# schematic.net
KiCad netlist of a schematic drawn in EAGLE
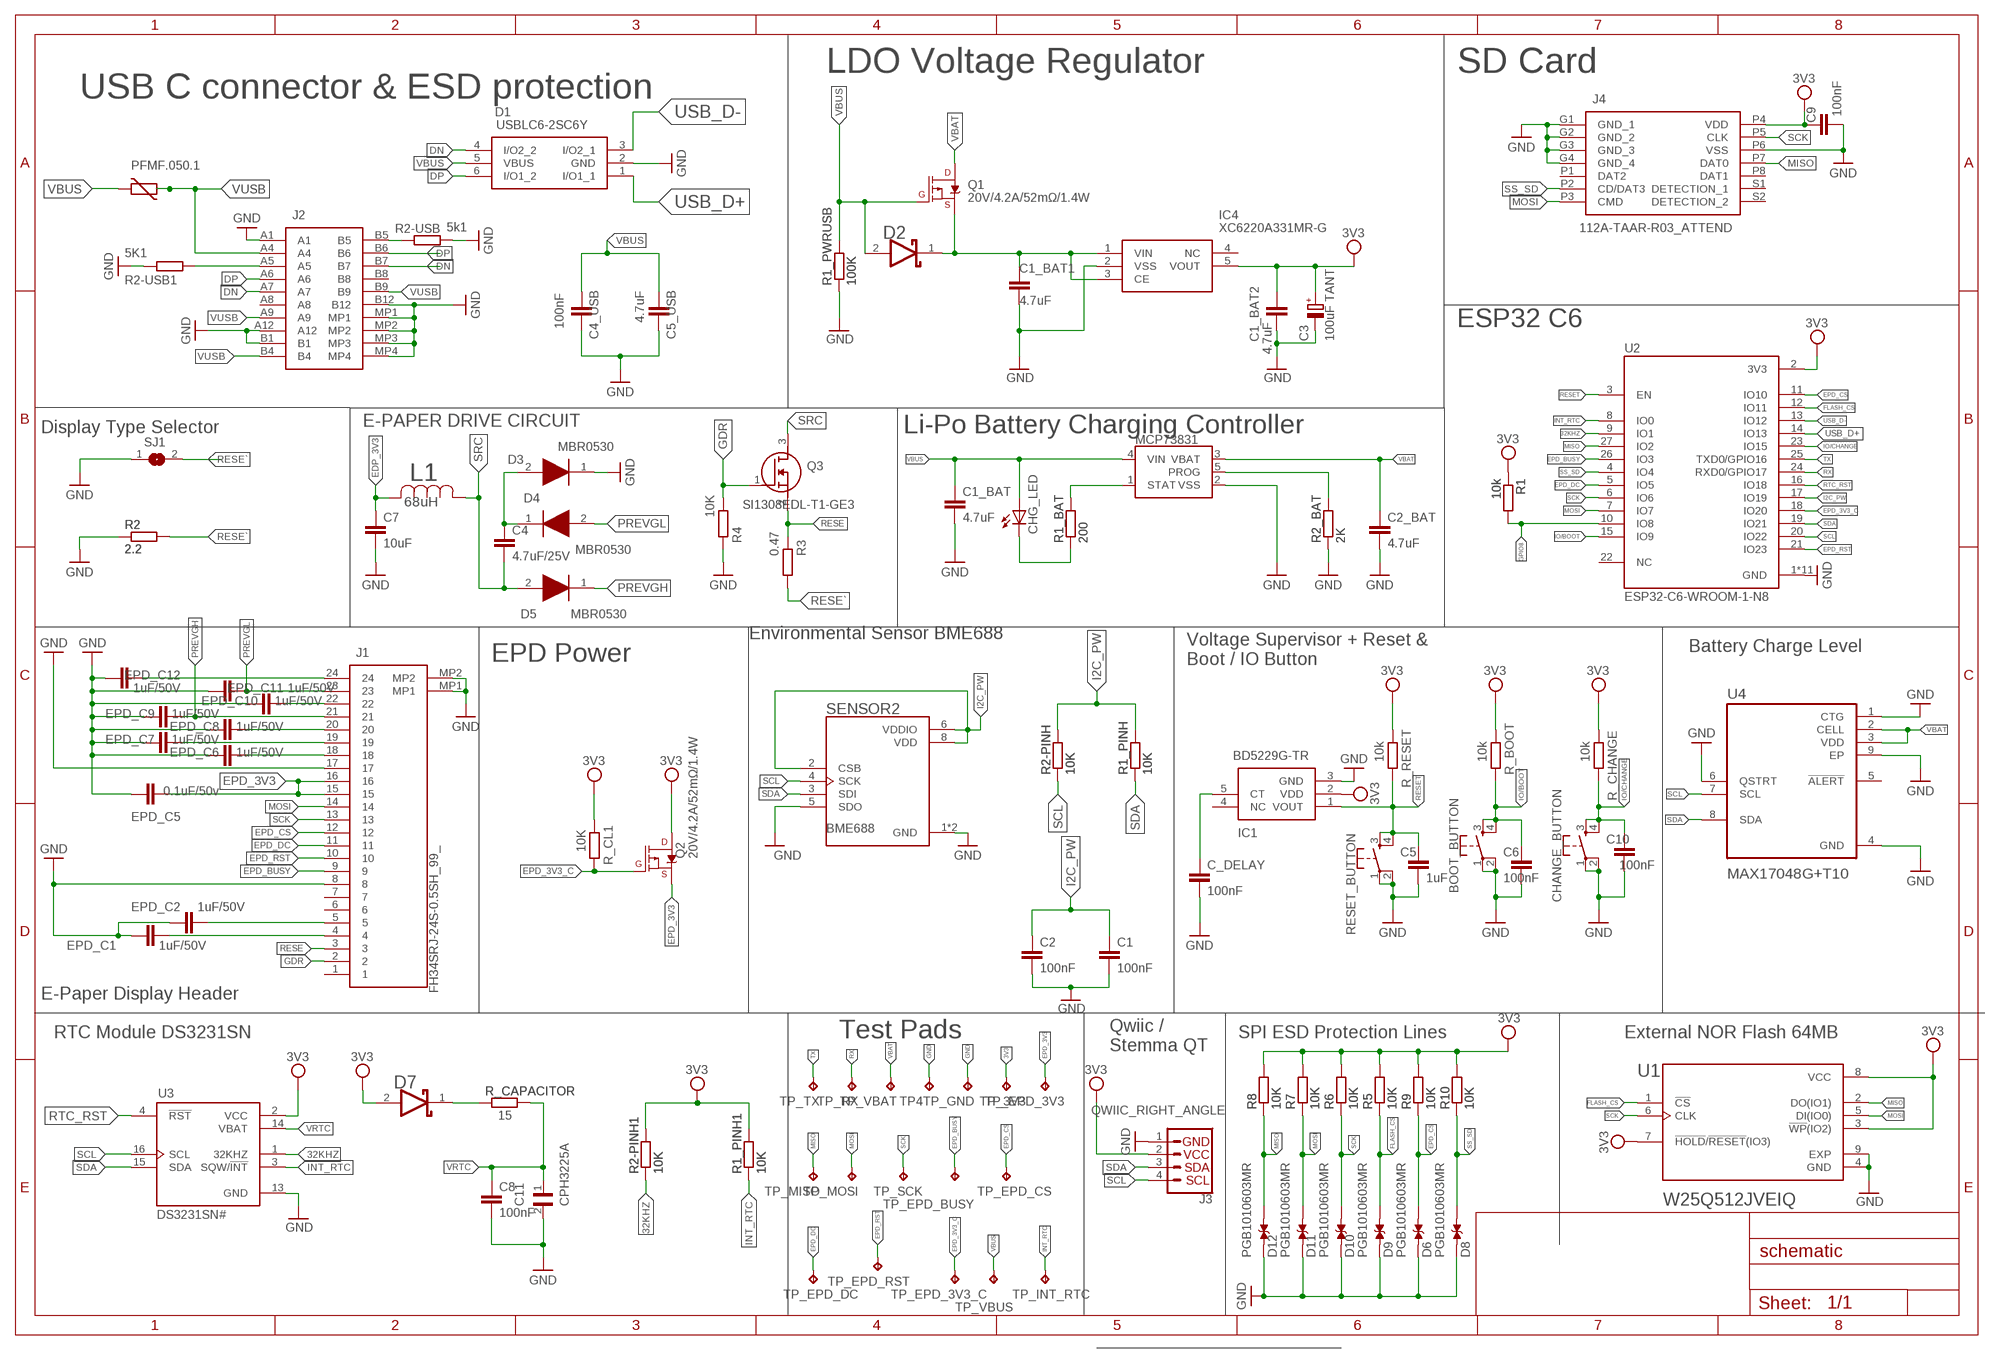
[diagram p0: schematic, sheet 1]

(export (version "E")
  (design (tool "Eeschema 10.0.6"))
  (components
    (comp (ref "BOOT_BUTTON")
      (value "BUTTON_CUSYOMV1")
      (footprint "eagle-import:MYBUTTON")
      (libsource (lib "eagle-import") (part "BUTTON_CUSYOMV1"))
    )
    (comp (ref "C1")
      (value "100nF")
      (footprint "eagle-import:EAGLE-LTSPICE_C0402")
      (libsource (lib "eagle-import") (part "EAGLE-LTSPICE_CC0402"))
    )
    (comp (ref "C1_BAT")
      (value "4.7uF")
      (footprint "eagle-import:EAGLE-LTSPICE_C0402")
      (libsource (lib "eagle-import") (part "EAGLE-LTSPICE_CC0402"))
    )
    (comp (ref "C1_BAT1")
      (value "4.7uF")
      (footprint "eagle-import:ESP32_WROVER_EAGLE-LTSPICE_C0402")
      (libsource (lib "eagle-import") (part "ESP32_WROVER_EAGLE-LTSPICE_CC0402"))
    )
    (comp (ref "C1_BAT2")
      (value "4.7uF")
      (footprint "eagle-import:ESP32_WROVER_EAGLE-LTSPICE_C0402")
      (libsource (lib "eagle-import") (part "ESP32_WROVER_EAGLE-LTSPICE_CC0402"))
    )
    (comp (ref "C2")
      (value "100nF")
      (footprint "eagle-import:EAGLE-LTSPICE_C0402")
      (libsource (lib "eagle-import") (part "EAGLE-LTSPICE_CC0402"))
    )
    (comp (ref "C2_BAT")
      (value "4.7uF")
      (footprint "eagle-import:EAGLE-LTSPICE_C0402")
      (libsource (lib "eagle-import") (part "EAGLE-LTSPICE_CC0402"))
    )
    (comp (ref "C3")
      (value "100uF TANT")
      (footprint "eagle-import:RCL_CT3528")
      (libsource (lib "eagle-import") (part "RCL_CPOL-EUCT3528"))
    )
    (comp (ref "C4")
      (value "4.7uF/25V")
      (footprint "eagle-import:EAGLE-LTSPICE_C0402")
      (libsource (lib "eagle-import") (part "EAGLE-LTSPICE_CC0402"))
    )
    (comp (ref "C4_USB")
      (value "100nF")
      (footprint "eagle-import:EAGLE-LTSPICE_C0402")
      (libsource (lib "eagle-import") (part "EAGLE-LTSPICE_CC0402"))
    )
    (comp (ref "C5")
      (value "1uF")
      (footprint "eagle-import:EAGLE-LTSPICE_C0402")
      (libsource (lib "eagle-import") (part "EAGLE-LTSPICE_CC0402"))
    )
    (comp (ref "C5_USB")
      (value "4.7uF")
      (footprint "eagle-import:EAGLE-LTSPICE_C0402")
      (libsource (lib "eagle-import") (part "EAGLE-LTSPICE_CC0402"))
    )
    (comp (ref "C6")
      (value "100nF")
      (footprint "eagle-import:EAGLE-LTSPICE_C0402")
      (libsource (lib "eagle-import") (part "EAGLE-LTSPICE_CC0402"))
    )
    (comp (ref "C7")
      (value "10uF")
      (footprint "eagle-import:EAGLE-LTSPICE_C0402")
      (libsource (lib "eagle-import") (part "EAGLE-LTSPICE_CC0402"))
    )
    (comp (ref "C8")
      (value "100nF")
      (footprint "eagle-import:EAGLE-LTSPICE_C0402")
      (libsource (lib "eagle-import") (part "EAGLE-LTSPICE_CC0402"))
    )
    (comp (ref "C9")
      (value "100nF")
      (footprint "eagle-import:EAGLE-LTSPICE_C0402")
      (libsource (lib "eagle-import") (part "EAGLE-LTSPICE_CC0402"))
    )
    (comp (ref "C10")
      (value "100nF")
      (footprint "eagle-import:EAGLE-LTSPICE_C0402")
      (libsource (lib "eagle-import") (part "EAGLE-LTSPICE_CC0402"))
    )
    (comp (ref "C11")
      (value "CPH3225A")
      (footprint "eagle-import:CAPCP3225X100N")
      (fields (field (name "MF") "Seiko Instruments"))
      (libsource (lib "eagle-import") (part "CPH3225A"))
    )
    (comp (ref "CHANGE_BUTTON")
      (value "BUTTON_CUSYOMV1")
      (footprint "eagle-import:MYBUTTON")
      (libsource (lib "eagle-import") (part "BUTTON_CUSYOMV1"))
    )
    (comp (ref "CHG_LED")
      (value "ADAFRUIT_LEDCHIP-LED0603")
      (footprint "eagle-import:ADAFRUIT_CHIP-LED0603")
      (libsource (lib "eagle-import") (part "ADAFRUIT_LEDCHIP-LED0603"))
    )
    (comp (ref "C_DELAY")
      (value "100nF")
      (footprint "eagle-import:EAGLE-LTSPICE_C0402")
      (libsource (lib "eagle-import") (part "EAGLE-LTSPICE_CC0402"))
    )
    (comp (ref "D1")
      (value "USBLC6-2SC6Y")
      (footprint "eagle-import:SOT95P280X145-6N")
      (fields (field (name "MF") "STMicroelectronics"))
      (libsource (lib "eagle-import") (part "USBLC6-2SC6Y"))
    )
    (comp (ref "D2")
      (value "ESP32_WROVER_AVX---SD0805S020S1R0_AVX_SD0805S020S1R0_0_0AVX_SD0805S020S1R0_0_0")
      (footprint "eagle-import:ESP32_WROVER_AVX---SD0805S020S1R0_AVX_SD0805S020S1R0_0")
      (fields
        (field (name "DIGIKEY_PART_NUMBER") "478-7800-1-ND")
        (field (name "MF") "AVX")
        (field (name "MOUSER_PART_NUMBER") "581-SD0805S020S1R0")
      )
      (libsource (lib "eagle-import") (part "ESP32_WROVER_AVX---SD0805S020S1R0_AVX_SD0805S020S1R0_0_0AVX_SD0805S020S1R0_0_0"))
    )
    (comp (ref "D3")
      (value "MBR0530")
      (footprint "eagle-import:SOD3716X135N")
      (fields (field (name "MF") "ON Semiconductor"))
      (libsource (lib "eagle-import") (part "MBR0530"))
    )
    (comp (ref "D4")
      (value "MBR0530")
      (footprint "eagle-import:SOD3716X135N")
      (fields (field (name "MF") "ON Semiconductor"))
      (libsource (lib "eagle-import") (part "MBR0530"))
    )
    (comp (ref "D5")
      (value "MBR0530")
      (footprint "eagle-import:SOD3716X135N")
      (fields (field (name "MF") "ON Semiconductor"))
      (libsource (lib "eagle-import") (part "MBR0530"))
    )
    (comp (ref "D6")
      (value "PGB1010603MR")
      (footprint "eagle-import:DIOC1608X36N")
      (fields (field (name "MF") "Littelfuse Inc."))
      (libsource (lib "eagle-import") (part "PGB1010603MR"))
    )
    (comp (ref "D7")
      (value "ESP32_WROVER_AVX---SD0805S020S1R0_AVX_SD0805S020S1R0_0_0AVX_SD0805S020S1R0_0_0")
      (footprint "eagle-import:ESP32_WROVER_AVX---SD0805S020S1R0_AVX_SD0805S020S1R0_0")
      (fields
        (field (name "DIGIKEY_PART_NUMBER") "478-7800-1-ND")
        (field (name "MF") "AVX")
        (field (name "MOUSER_PART_NUMBER") "581-SD0805S020S1R0")
      )
      (libsource (lib "eagle-import") (part "ESP32_WROVER_AVX---SD0805S020S1R0_AVX_SD0805S020S1R0_0_0AVX_SD0805S020S1R0_0_0"))
    )
    (comp (ref "D8")
      (value "PGB1010603MR")
      (footprint "eagle-import:DIOC1608X36N")
      (fields (field (name "MF") "Littelfuse Inc."))
      (libsource (lib "eagle-import") (part "PGB1010603MR"))
    )
    (comp (ref "D9")
      (value "PGB1010603MR")
      (footprint "eagle-import:DIOC1608X36N")
      (fields (field (name "MF") "Littelfuse Inc."))
      (libsource (lib "eagle-import") (part "PGB1010603MR"))
    )
    (comp (ref "D10")
      (value "PGB1010603MR")
      (footprint "eagle-import:DIOC1608X36N")
      (fields (field (name "MF") "Littelfuse Inc."))
      (libsource (lib "eagle-import") (part "PGB1010603MR"))
    )
    (comp (ref "D11")
      (value "PGB1010603MR")
      (footprint "eagle-import:DIOC1608X36N")
      (fields (field (name "MF") "Littelfuse Inc."))
      (libsource (lib "eagle-import") (part "PGB1010603MR"))
    )
    (comp (ref "D12")
      (value "PGB1010603MR")
      (footprint "eagle-import:DIOC1608X36N")
      (fields (field (name "MF") "Littelfuse Inc."))
      (libsource (lib "eagle-import") (part "PGB1010603MR"))
    )
    (comp (ref "EPD_C1")
      (value "1uF/50V")
      (footprint "eagle-import:EAGLE-LTSPICE_C0402")
      (libsource (lib "eagle-import") (part "EAGLE-LTSPICE_CC0402"))
    )
    (comp (ref "EPD_C2")
      (value "1uF/50V")
      (footprint "eagle-import:EAGLE-LTSPICE_C0402")
      (libsource (lib "eagle-import") (part "EAGLE-LTSPICE_CC0402"))
    )
    (comp (ref "EPD_C5")
      (value "0.1uF/50v")
      (footprint "eagle-import:EAGLE-LTSPICE_C0402")
      (libsource (lib "eagle-import") (part "EAGLE-LTSPICE_CC0402"))
    )
    (comp (ref "EPD_C6")
      (value "1uF/50V")
      (footprint "eagle-import:EAGLE-LTSPICE_C0402")
      (libsource (lib "eagle-import") (part "EAGLE-LTSPICE_CC0402"))
    )
    (comp (ref "EPD_C7")
      (value "1uF/50V")
      (footprint "eagle-import:EAGLE-LTSPICE_C0402")
      (libsource (lib "eagle-import") (part "EAGLE-LTSPICE_CC0402"))
    )
    (comp (ref "EPD_C8")
      (value "1uF/50V")
      (footprint "eagle-import:EAGLE-LTSPICE_C0402")
      (libsource (lib "eagle-import") (part "EAGLE-LTSPICE_CC0402"))
    )
    (comp (ref "EPD_C9")
      (value "1uF/50V")
      (footprint "eagle-import:EAGLE-LTSPICE_C0402")
      (libsource (lib "eagle-import") (part "EAGLE-LTSPICE_CC0402"))
    )
    (comp (ref "EPD_C10")
      (value "1uF/50V")
      (footprint "eagle-import:EAGLE-LTSPICE_C0402")
      (libsource (lib "eagle-import") (part "EAGLE-LTSPICE_CC0402"))
    )
    (comp (ref "EPD_C11")
      (value "1uF/50V")
      (footprint "eagle-import:EAGLE-LTSPICE_C0402")
      (libsource (lib "eagle-import") (part "EAGLE-LTSPICE_CC0402"))
    )
    (comp (ref "EPD_C12")
      (value "1uF/50V")
      (footprint "eagle-import:EAGLE-LTSPICE_C0402")
      (libsource (lib "eagle-import") (part "EAGLE-LTSPICE_CC0402"))
    )
    (comp (ref "IC1")
      (value "BD5229G-TR")
      (footprint "eagle-import:SOT95P280X125-5N")
      (fields (field (name "MOUSER_PART_NUMBER") "755-BD5229G-TR"))
      (libsource (lib "eagle-import") (part "BD5229G-TR"))
    )
    (comp (ref "IC4")
      (value "XC6220A331MR-G")
      (footprint "eagle-import:SOT95P280X120-5N")
      (fields (field (name "MOUSER_PART_NUMBER") "865-XC6220A331MR-G"))
      (libsource (lib "eagle-import") (part "XC6220A331MR-G"))
    )
    (comp (ref "J1")
      (value "FH34SRJ-24S-0.5SH_99_")
      (footprint "eagle-import:FH34SRJ24S05SH99")
      (fields
        (field (name "MANUFACTURER_PART_NUMBER") "FH34SRJ-24S-0.5SH(99)")
        (field (name "MOUSER_PART_NUMBER") "798-FH34SRJ24S05SH99")
      )
      (libsource (lib "eagle-import") (part "FH34SRJ-24S-0.5SH_99_"))
    )
    (comp (ref "J2")
      (value "SAMACSYS_PARTS_USB4110-GF-A")
      (footprint "eagle-import:SAMACSYS_PARTS_USB4110GFA")
      (fields
        (field (name "MANUFACTURER_PART_NUMBER") "USB4110-GF-A")
        (field (name "MOUSER_PART_NUMBER") "640-USB4110-GF-A")
      )
      (libsource (lib "eagle-import") (part "SAMACSYS_PARTS_USB4110-GF-A"))
    )
    (comp (ref "J3")
      (value "QWIIC_RIGHT_ANGLE")
      (footprint "eagle-import:JST04_1MM_RA")
      (libsource (lib "eagle-import") (part "QWIIC_CONNECTORJS-1MM"))
    )
    (comp (ref "J4")
      (value "112A-TAAR-R03_ATTEND")
      (footprint "eagle-import:112ATAARR03ATTEND")
      (fields (field (name "MANUFACTURER_PART_NUMBER") "112A-TAAR-R03 ATTEND"))
      (libsource (lib "eagle-import") (part "112A-TAAR-R03_ATTEND"))
    )
    (comp (ref "L1")
      (value "68uH")
      (footprint "eagle-import:IND_4828-WE-TPC_WRE")
      (fields
        (field (name "MANUFACTURER_PART_NUMBER") "744043680")
        (field (name "COPYRIGHT") "Copyright (C) 2024 Ultra Librarian. All rights reserved.")
      )
      (libsource (lib "eagle-import") (part "744043680IND_4828-WE-TPC_WRE"))
    )
    (comp (ref "MCP73831")
      (value "ESP32_WROVER_SPARKFUN-IC-POWER_MCP73831")
      (footprint "eagle-import:ESP32_WROVER_SPARKFUN-IC-POWER_SOT23-5")
      (libsource (lib "eagle-import") (part "ESP32_WROVER_SPARKFUN-IC-POWER_MCP73831"))
    )
    (comp (ref "PFMF.050.1")
      (value "ESP32C6_VARISTORCN1812")
      (footprint "eagle-import:ESP32C6_VARISTOR_CT_CN1812")
      (libsource (lib "eagle-import") (part "ESP32C6_VARISTORCN1812"))
    )
    (comp (ref "Q1")
      (value "20V/4.2A/52mΩ/1.4W")
      (footprint "eagle-import:ESP32_WROVER_SPARKFUN-DISCRETESEMI_SOT23-3")
      (libsource (lib "eagle-import") (part "ESP32_WROVER_SPARKFUN-DISCRETESEMI_MOSFET_PCH-DMG2305UX-7"))
    )
    (comp (ref "Q2")
      (value "20V/4.2A/52mΩ/1.4W")
      (footprint "eagle-import:ESP32_WROVER_SPARKFUN-DISCRETESEMI_SOT23-3")
      (libsource (lib "eagle-import") (part "ESP32_WROVER_SPARKFUN-DISCRETESEMI_MOSFET_PCH-DMG2305UX-7"))
    )
    (comp (ref "Q3")
      (value "SI1308EDL-T1-GE3")
      (footprint "eagle-import:SOT65P210X110-3N")
      (fields (field (name "MF") "Vishay Siliconix"))
      (libsource (lib "eagle-import") (part "SI1308EDL-T1-GE3"))
    )
    (comp (ref "R1")
      (value "10k")
      (footprint "eagle-import:ESP32_WROVER_EAGLE-LTSPICE_R0402")
      (libsource (lib "eagle-import") (part "ESP32_WROVER_EAGLE-LTSPICE_RR0402"))
    )
    (comp (ref "R1_BAT")
      (value "200")
      (footprint "eagle-import:ESP32_WROVER_EAGLE-LTSPICE_R0402")
      (libsource (lib "eagle-import") (part "ESP32_WROVER_EAGLE-LTSPICE_RR0402"))
    )
    (comp (ref "R1_PINH")
      (value "10K")
      (footprint "eagle-import:ESP32_WROVER_EAGLE-LTSPICE_R0402")
      (libsource (lib "eagle-import") (part "ESP32_WROVER_EAGLE-LTSPICE_RR0402"))
    )
    (comp (ref "R1_PINH1")
      (value "10K")
      (footprint "eagle-import:ESP32_WROVER_EAGLE-LTSPICE_R0402")
      (libsource (lib "eagle-import") (part "ESP32_WROVER_EAGLE-LTSPICE_RR0402"))
    )
    (comp (ref "R1_PWRUSB")
      (value "100K")
      (footprint "eagle-import:ESP32_WROVER_EAGLE-LTSPICE_R0402")
      (libsource (lib "eagle-import") (part "ESP32_WROVER_EAGLE-LTSPICE_RR0402"))
    )
    (comp (ref "R2")
      (value "2.2")
      (footprint "eagle-import:ESP32_WROVER_EAGLE-LTSPICE_R0402")
      (libsource (lib "eagle-import") (part "ESP32_WROVER_EAGLE-LTSPICE_RR0402"))
    )
    (comp (ref "R2-PINH")
      (value "10K")
      (footprint "eagle-import:ESP32_WROVER_EAGLE-LTSPICE_R0402")
      (libsource (lib "eagle-import") (part "ESP32_WROVER_EAGLE-LTSPICE_RR0402"))
    )
    (comp (ref "R2-PINH1")
      (value "10K")
      (footprint "eagle-import:ESP32_WROVER_EAGLE-LTSPICE_R0402")
      (libsource (lib "eagle-import") (part "ESP32_WROVER_EAGLE-LTSPICE_RR0402"))
    )
    (comp (ref "R2-USB")
      (value "5k1")
      (footprint "eagle-import:ESP32_WROVER_EAGLE-LTSPICE_R0402")
      (libsource (lib "eagle-import") (part "ESP32_WROVER_EAGLE-LTSPICE_RR0402"))
    )
    (comp (ref "R2-USB1")
      (value "5K1")
      (footprint "eagle-import:ESP32_WROVER_EAGLE-LTSPICE_R0402")
      (fields (field (name "SPICEPREFIX") "R2-USB1"))
      (libsource (lib "eagle-import") (part "ESP32_WROVER_EAGLE-LTSPICE_RR0402"))
    )
    (comp (ref "R2_BAT")
      (value "2K")
      (footprint "eagle-import:ESP32_WROVER_EAGLE-LTSPICE_R0402")
      (libsource (lib "eagle-import") (part "ESP32_WROVER_EAGLE-LTSPICE_RR0402"))
    )
    (comp (ref "R3")
      (value "0.47")
      (footprint "eagle-import:ESP32_WROVER_EAGLE-LTSPICE_R0402")
      (libsource (lib "eagle-import") (part "ESP32_WROVER_EAGLE-LTSPICE_RR0402"))
    )
    (comp (ref "R4")
      (value "10K")
      (footprint "eagle-import:ESP32_WROVER_EAGLE-LTSPICE_R0402")
      (libsource (lib "eagle-import") (part "ESP32_WROVER_EAGLE-LTSPICE_RR0402"))
    )
    (comp (ref "R5")
      (value "10K")
      (footprint "eagle-import:ESP32_WROVER_EAGLE-LTSPICE_R0402")
      (libsource (lib "eagle-import") (part "ESP32_WROVER_EAGLE-LTSPICE_RR0402"))
    )
    (comp (ref "R6")
      (value "10K")
      (footprint "eagle-import:ESP32_WROVER_EAGLE-LTSPICE_R0402")
      (libsource (lib "eagle-import") (part "ESP32_WROVER_EAGLE-LTSPICE_RR0402"))
    )
    (comp (ref "R7")
      (value "10K")
      (footprint "eagle-import:ESP32_WROVER_EAGLE-LTSPICE_R0402")
      (libsource (lib "eagle-import") (part "ESP32_WROVER_EAGLE-LTSPICE_RR0402"))
    )
    (comp (ref "R8")
      (value "10K")
      (footprint "eagle-import:ESP32_WROVER_EAGLE-LTSPICE_R0402")
      (libsource (lib "eagle-import") (part "ESP32_WROVER_EAGLE-LTSPICE_RR0402"))
    )
    (comp (ref "R9")
      (value "10K")
      (footprint "eagle-import:ESP32_WROVER_EAGLE-LTSPICE_R0402")
      (libsource (lib "eagle-import") (part "ESP32_WROVER_EAGLE-LTSPICE_RR0402"))
    )
    (comp (ref "R10")
      (value "10K")
      (footprint "eagle-import:ESP32_WROVER_EAGLE-LTSPICE_R0402")
      (libsource (lib "eagle-import") (part "ESP32_WROVER_EAGLE-LTSPICE_RR0402"))
    )
    (comp (ref "RESET_BUTTON")
      (value "BUTTON_CUSYOMV1")
      (footprint "eagle-import:MYBUTTON")
      (libsource (lib "eagle-import") (part "BUTTON_CUSYOMV1"))
    )
    (comp (ref "R_BOOT")
      (value "10k")
      (footprint "eagle-import:ESP32_WROVER_EAGLE-LTSPICE_R0402")
      (libsource (lib "eagle-import") (part "ESP32_WROVER_EAGLE-LTSPICE_RR0402"))
    )
    (comp (ref "R_CAPACITOR")
      (value "15")
      (footprint "eagle-import:ESP32_WROVER_EAGLE-LTSPICE_R0402")
      (libsource (lib "eagle-import") (part "ESP32_WROVER_EAGLE-LTSPICE_RR0402"))
    )
    (comp (ref "R_CHANGE")
      (value "10k")
      (footprint "eagle-import:ESP32_WROVER_EAGLE-LTSPICE_R0402")
      (libsource (lib "eagle-import") (part "ESP32_WROVER_EAGLE-LTSPICE_RR0402"))
    )
    (comp (ref "R_CL1")
      (value "10K")
      (footprint "eagle-import:ESP32_WROVER_EAGLE-LTSPICE_R0402")
      (libsource (lib "eagle-import") (part "ESP32_WROVER_EAGLE-LTSPICE_RR0402"))
    )
    (comp (ref "R_RESET")
      (value "10k")
      (footprint "eagle-import:ESP32_WROVER_EAGLE-LTSPICE_R0402")
      (libsource (lib "eagle-import") (part "ESP32_WROVER_EAGLE-LTSPICE_RR0402"))
    )
    (comp (ref "SENSOR2")
      (value "ESP32_WROVER_BME680_BME680")
      (footprint "eagle-import:ESP32_WROVER_BME680_PSON80P300X300X100-8N")
      (fields (field (name "MF") "Bosch Sensortec") (field (name "MP") "BME680"))
      (libsource (lib "eagle-import") (part "ESP32_WROVER_BME680_BME680"))
    )
    (comp (ref "SJ1") (value "SJ") (footprint "eagle-import:SJ") (libsource (lib "eagle-import") (part "SJ")))
    (comp (ref "TP4")
      (value "TPTP20R")
      (footprint "eagle-import:TP20R")
      (libsource (lib "eagle-import") (part "TPTP20R"))
    )
    (comp (ref "TP_3V3")
      (value "TPTP20R")
      (footprint "eagle-import:TP20R")
      (libsource (lib "eagle-import") (part "TPTP20R"))
    )
    (comp (ref "TP_EPD_3V3")
      (value "TPTP20R")
      (footprint "eagle-import:TP20R")
      (libsource (lib "eagle-import") (part "TPTP20R"))
    )
    (comp (ref "TP_EPD_3V3_C")
      (value "TPTP20R")
      (footprint "eagle-import:TP20R")
      (libsource (lib "eagle-import") (part "TPTP20R"))
    )
    (comp (ref "TP_EPD_BUSY")
      (value "TPTP20R")
      (footprint "eagle-import:TP20R")
      (libsource (lib "eagle-import") (part "TPTP20R"))
    )
    (comp (ref "TP_EPD_CS")
      (value "TPTP20R")
      (footprint "eagle-import:TP20R")
      (libsource (lib "eagle-import") (part "TPTP20R"))
    )
    (comp (ref "TP_EPD_DC")
      (value "TPTP20R")
      (footprint "eagle-import:TP20R")
      (libsource (lib "eagle-import") (part "TPTP20R"))
    )
    (comp (ref "TP_EPD_RST")
      (value "TPTP20R")
      (footprint "eagle-import:TP20R")
      (libsource (lib "eagle-import") (part "TPTP20R"))
    )
    (comp (ref "TP_GND")
      (value "TPTP20R")
      (footprint "eagle-import:TP20R")
      (libsource (lib "eagle-import") (part "TPTP20R"))
    )
    (comp (ref "TP_INT_RTC")
      (value "TPTP20R")
      (footprint "eagle-import:TP20R")
      (libsource (lib "eagle-import") (part "TPTP20R"))
    )
    (comp (ref "TP_MISO")
      (value "TPTP20R")
      (footprint "eagle-import:TP20R")
      (libsource (lib "eagle-import") (part "TPTP20R"))
    )
    (comp (ref "TP_MOSI")
      (value "TPTP20R")
      (footprint "eagle-import:TP20R")
      (libsource (lib "eagle-import") (part "TPTP20R"))
    )
    (comp (ref "TP_RX")
      (value "TPTP20R")
      (footprint "eagle-import:TP20R")
      (libsource (lib "eagle-import") (part "TPTP20R"))
    )
    (comp (ref "TP_SCK")
      (value "TPTP20R")
      (footprint "eagle-import:TP20R")
      (libsource (lib "eagle-import") (part "TPTP20R"))
    )
    (comp (ref "TP_TX")
      (value "TPTP20R")
      (footprint "eagle-import:TP20R")
      (libsource (lib "eagle-import") (part "TPTP20R"))
    )
    (comp (ref "TP_VBAT")
      (value "TPTP20R")
      (footprint "eagle-import:TP20R")
      (libsource (lib "eagle-import") (part "TPTP20R"))
    )
    (comp (ref "TP_VBUS")
      (value "TPTP20R")
      (footprint "eagle-import:TP20R")
      (libsource (lib "eagle-import") (part "TPTP20R"))
    )
    (comp (ref "U1")
      (value "W25Q512JVEIQ")
      (footprint "eagle-import:SON127P600X800X80-9N")
      (fields (field (name "MF") "Winbond Electronics"))
      (libsource (lib "eagle-import") (part "W25Q512JVEIQ"))
    )
    (comp (ref "U2")
      (value "ESP32-C6-WROOM-1-N8")
      (footprint "eagle-import:XCVR_ESP32-C6-WROOM-1-N8")
      (fields (field (name "MF") "Espressif Systems"))
      (libsource (lib "eagle-import") (part "ESP32-C6-WROOM-1-N8"))
    )
    (comp (ref "U3")
      (value "DS3231SN#")
      (footprint "eagle-import:SOIC127P1032X265-16N")
      (fields (field (name "MF") "Analog Devices"))
      (libsource (lib "eagle-import") (part "DS3231SN#"))
    )
    (comp (ref "U4")
      (value "MAX17048G+T10")
      (footprint "eagle-import:SON50P200X200X80-9N")
      (fields (field (name "MF") "Analog Devices"))
      (libsource (lib "eagle-import") (part "MAX17048G+T10"))
    )
  )
  (nets
    (net (code "1") (name "3V3") (class "Default")
      (node (ref "C1_BAT2") (pin "1") (pinfunction "1_1") (pintype "passive"))
      (node (ref "C3") (pin "+") (pinfunction "+_+") (pintype "passive"))
      (node (ref "C9") (pin "2") (pinfunction "2_2") (pintype "passive"))
      (node (ref "D7") (pin "2") (pinfunction "ANODE_2") (pintype "bidirectional"))
      (node (ref "IC1") (pin "2") (pinfunction "VDD_2") (pintype "bidirectional"))
      (node (ref "IC4") (pin "5") (pinfunction "VOUT_5") (pintype "bidirectional"))
      (node (ref "J3") (pin "2") (pinfunction "2_2") (pintype "power_in"))
      (node (ref "J4") (pin "P4") (pinfunction "VDD_P4") (pintype "bidirectional"))
      (node (ref "Q2") (pin "3") (pinfunction "D_3") (pintype "bidirectional"))
      (node (ref "R1") (pin "1") (pinfunction "1_1") (pintype "passive"))
      (node (ref "R10") (pin "2") (pinfunction "2_2") (pintype "passive"))
      (node (ref "R1_PINH1") (pin "2") (pinfunction "2_2") (pintype "passive"))
      (node (ref "R2-PINH1") (pin "2") (pinfunction "2_2") (pintype "passive"))
      (node (ref "R5") (pin "2") (pinfunction "2_2") (pintype "passive"))
      (node (ref "R6") (pin "2") (pinfunction "2_2") (pintype "passive"))
      (node (ref "R7") (pin "2") (pinfunction "2_2") (pintype "passive"))
      (node (ref "R8") (pin "2") (pinfunction "2_2") (pintype "passive"))
      (node (ref "R9") (pin "2") (pinfunction "2_2") (pintype "passive"))
      (node (ref "R_BOOT") (pin "2") (pinfunction "2_2") (pintype "passive"))
      (node (ref "R_CHANGE") (pin "2") (pinfunction "2_2") (pintype "passive"))
      (node (ref "R_CL1") (pin "2") (pinfunction "2_2") (pintype "passive"))
      (node (ref "R_RESET") (pin "2") (pinfunction "2_2") (pintype "passive"))
      (node (ref "TP_3V3") (pin "TP") (pinfunction "TP_TP") (pintype "input"))
      (node (ref "U1") (pin "3") (pinfunction "~{WP}(IO2)_3") (pintype "bidirectional"))
      (node (ref "U1") (pin "7") (pinfunction "~{HOLD}/~{RESET}(IO3)_7") (pintype "bidirectional"))
      (node (ref "U1") (pin "8") (pinfunction "VCC_8") (pintype "power_in"))
      (node (ref "U2") (pin "2") (pinfunction "3V3_2") (pintype "power_in"))
      (node (ref "U3") (pin "2") (pinfunction "VCC_2") (pintype "power_in"))
    )
    (net (code "2") (name "32KHZ") (class "Default")
      (node (ref "R2-PINH1") (pin "1") (pinfunction "1_1") (pintype "passive"))
      (node (ref "U2") (pin "9") (pinfunction "IO1_9") (pintype "bidirectional"))
      (node (ref "U3") (pin "1") (pinfunction "32KHZ_1") (pintype "output"))
    )
    (net (code "3") (name "DN") (class "Default")
      (node (ref "D1") (pin "4") (pinfunction "I/O2_2_4") (pintype "bidirectional"))
      (node (ref "J2") (pin "A7") (pinfunction "A7_A7") (pintype "bidirectional"))
      (node (ref "J2") (pin "B7") (pinfunction "B7_B7") (pintype "bidirectional"))
    )
    (net (code "4") (name "DP") (class "Default")
      (node (ref "D1") (pin "6") (pinfunction "I/O1_2_6") (pintype "bidirectional"))
      (node (ref "J2") (pin "A6") (pinfunction "A6_A6") (pintype "bidirectional"))
      (node (ref "J2") (pin "B6") (pinfunction "B6_B6") (pintype "bidirectional"))
    )
    (net (code "5") (name "EDP_3V3") (class "Default")
      (node (ref "C7") (pin "1") (pinfunction "1_1") (pintype "passive"))
      (node (ref "L1") (pin "2") (pinfunction "2_2") (pintype "passive"))
    )
    (net (code "6") (name "EPD_3V3") (class "Default")
      (node (ref "EPD_C5") (pin "2") (pinfunction "2_2") (pintype "passive"))
      (node (ref "J1") (pin "15") (pinfunction "15_15") (pintype "bidirectional"))
      (node (ref "J1") (pin "16") (pinfunction "16_16") (pintype "bidirectional"))
      (node (ref "Q2") (pin "2") (pinfunction "S_2") (pintype "bidirectional"))
      (node (ref "TP_EPD_3V3") (pin "TP") (pinfunction "TP_TP") (pintype "input"))
    )
    (net (code "7") (name "EPD_3V3_C") (class "Default")
      (node (ref "Q2") (pin "1") (pinfunction "G_1") (pintype "bidirectional"))
      (node (ref "R_CL1") (pin "1") (pinfunction "1_1") (pintype "passive"))
      (node (ref "TP_EPD_3V3_C") (pin "TP") (pinfunction "TP_TP") (pintype "input"))
      (node (ref "U2") (pin "18") (pinfunction "IO20_18") (pintype "bidirectional"))
    )
    (net (code "8") (name "EPD_BUSY") (class "Default")
      (node (ref "J1") (pin "9") (pinfunction "9_9") (pintype "bidirectional"))
      (node (ref "TP_EPD_BUSY") (pin "TP") (pinfunction "TP_TP") (pintype "input"))
      (node (ref "U2") (pin "26") (pinfunction "IO3_26") (pintype "bidirectional"))
    )
    (net (code "9") (name "EPD_CS") (class "Default")
      (node (ref "D6") (pin "2") (pinfunction "2_2") (pintype "passive"))
      (node (ref "J1") (pin "12") (pinfunction "12_12") (pintype "bidirectional"))
      (node (ref "R9") (pin "1") (pinfunction "1_1") (pintype "passive"))
      (node (ref "TP_EPD_CS") (pin "TP") (pinfunction "TP_TP") (pintype "input"))
      (node (ref "U2") (pin "11") (pinfunction "IO10_11") (pintype "bidirectional"))
    )
    (net (code "10") (name "EPD_DC") (class "Default")
      (node (ref "J1") (pin "11") (pinfunction "11_11") (pintype "bidirectional"))
      (node (ref "TP_EPD_DC") (pin "TP") (pinfunction "TP_TP") (pintype "input"))
      (node (ref "U2") (pin "5") (pinfunction "IO5_5") (pintype "bidirectional"))
    )
    (net (code "11") (name "EPD_RST") (class "Default")
      (node (ref "J1") (pin "10") (pinfunction "10_10") (pintype "bidirectional"))
      (node (ref "TP_EPD_RST") (pin "TP") (pinfunction "TP_TP") (pintype "input"))
      (node (ref "U2") (pin "21") (pinfunction "IO23_21") (pintype "bidirectional"))
    )
    (net (code "12") (name "FLASH_CS") (class "Default")
      (node (ref "D9") (pin "2") (pinfunction "2_2") (pintype "passive"))
      (node (ref "R5") (pin "1") (pinfunction "1_1") (pintype "passive"))
      (node (ref "U1") (pin "1") (pinfunction "~{CS}_1") (pintype "input"))
      (node (ref "U2") (pin "12") (pinfunction "IO11_12") (pintype "bidirectional"))
    )
    (net (code "13") (name "GDR") (class "Default")
      (node (ref "J1") (pin "2") (pinfunction "2_2") (pintype "bidirectional"))
      (node (ref "Q3") (pin "1") (pinfunction "G_1") (pintype "bidirectional"))
      (node (ref "R4") (pin "2") (pinfunction "2_2") (pintype "passive"))
    )
    (net (code "14") (name "GND") (class "Default")
      (node (ref "BOOT_BUTTON") (pin "1") (pinfunction "1_1") (pintype "passive"))
      (node (ref "BOOT_BUTTON") (pin "2") (pinfunction "2_2") (pintype "passive"))
      (node (ref "C1") (pin "2") (pinfunction "2_2") (pintype "passive"))
      (node (ref "C10") (pin "2") (pinfunction "2_2") (pintype "passive"))
      (node (ref "C11") (pin "2") (pinfunction "2_2") (pintype "passive"))
      (node (ref "C1_BAT") (pin "2") (pinfunction "2_2") (pintype "passive"))
      (node (ref "C1_BAT1") (pin "2") (pinfunction "2_2") (pintype "passive"))
      (node (ref "C1_BAT2") (pin "2") (pinfunction "2_2") (pintype "passive"))
      (node (ref "C2") (pin "2") (pinfunction "2_2") (pintype "passive"))
      (node (ref "C2_BAT") (pin "2") (pinfunction "2_2") (pintype "passive"))
      (node (ref "C3") (pin "-") (pinfunction "-_-") (pintype "passive"))
      (node (ref "C4_USB") (pin "2") (pinfunction "2_2") (pintype "passive"))
      (node (ref "C5") (pin "2") (pinfunction "2_2") (pintype "passive"))
      (node (ref "C5_USB") (pin "2") (pinfunction "2_2") (pintype "passive"))
      (node (ref "C6") (pin "2") (pinfunction "2_2") (pintype "passive"))
      (node (ref "C7") (pin "2") (pinfunction "2_2") (pintype "passive"))
      (node (ref "C8") (pin "2") (pinfunction "2_2") (pintype "passive"))
      (node (ref "C9") (pin "1") (pinfunction "1_1") (pintype "passive"))
      (node (ref "CHANGE_BUTTON") (pin "1") (pinfunction "1_1") (pintype "passive"))
      (node (ref "CHANGE_BUTTON") (pin "2") (pinfunction "2_2") (pintype "passive"))
      (node (ref "C_DELAY") (pin "2") (pinfunction "2_2") (pintype "passive"))
      (node (ref "D1") (pin "2") (pinfunction "GND_2") (pintype "bidirectional"))
      (node (ref "D10") (pin "1") (pinfunction "1_1") (pintype "passive"))
      (node (ref "D11") (pin "1") (pinfunction "1_1") (pintype "passive"))
      (node (ref "D12") (pin "1") (pinfunction "1_1") (pintype "passive"))
      (node (ref "D3") (pin "1") (pinfunction "K_1") (pintype "bidirectional"))
      (node (ref "D6") (pin "1") (pinfunction "1_1") (pintype "passive"))
      (node (ref "D8") (pin "1") (pinfunction "1_1") (pintype "passive"))
      (node (ref "D9") (pin "1") (pinfunction "1_1") (pintype "passive"))
      (node (ref "EPD_C1") (pin "1") (pinfunction "1_1") (pintype "passive"))
      (node (ref "EPD_C10") (pin "1") (pinfunction "1_1") (pintype "passive"))
      (node (ref "EPD_C11") (pin "1") (pinfunction "1_1") (pintype "passive"))
      (node (ref "EPD_C12") (pin "1") (pinfunction "1_1") (pintype "passive"))
      (node (ref "EPD_C2") (pin "1") (pinfunction "1_1") (pintype "passive"))
      (node (ref "EPD_C5") (pin "1") (pinfunction "1_1") (pintype "passive"))
      (node (ref "EPD_C6") (pin "1") (pinfunction "1_1") (pintype "passive"))
      (node (ref "EPD_C7") (pin "1") (pinfunction "1_1") (pintype "passive"))
      (node (ref "EPD_C8") (pin "1") (pinfunction "1_1") (pintype "passive"))
      (node (ref "EPD_C9") (pin "1") (pinfunction "1_1") (pintype "passive"))
      (node (ref "IC1") (pin "3") (pinfunction "GND_3") (pintype "bidirectional"))
      (node (ref "IC4") (pin "2") (pinfunction "VSS_2") (pintype "bidirectional"))
      (node (ref "J1") (pin "17") (pinfunction "17_17") (pintype "bidirectional"))
      (node (ref "J1") (pin "8") (pinfunction "8_8") (pintype "bidirectional"))
      (node (ref "J1") (pin "MP1") (pinfunction "MP1_MP1") (pintype "bidirectional"))
      (node (ref "J1") (pin "MP2") (pinfunction "MP2_MP2") (pintype "bidirectional"))
      (node (ref "J2") (pin "A1") (pinfunction "A1_A1") (pintype "bidirectional"))
      (node (ref "J2") (pin "A12") (pinfunction "A12_A12") (pintype "bidirectional"))
      (node (ref "J2") (pin "B1") (pinfunction "B1_B1") (pintype "bidirectional"))
      (node (ref "J2") (pin "B12") (pinfunction "B12_B12") (pintype "bidirectional"))
      (node (ref "J2") (pin "MP1") (pinfunction "MP1_MP1") (pintype "bidirectional"))
      (node (ref "J2") (pin "MP2") (pinfunction "MP2_MP2") (pintype "bidirectional"))
      (node (ref "J2") (pin "MP3") (pinfunction "MP3_MP3") (pintype "bidirectional"))
      (node (ref "J2") (pin "MP4") (pinfunction "MP4_MP4") (pintype "bidirectional"))
      (node (ref "J3") (pin "1") (pinfunction "1_1") (pintype "power_in"))
      (node (ref "J4") (pin "G1") (pinfunction "GND_1_G1") (pintype "bidirectional"))
      (node (ref "J4") (pin "G2") (pinfunction "GND_2_G2") (pintype "bidirectional"))
      (node (ref "J4") (pin "G3") (pinfunction "GND_3_G3") (pintype "bidirectional"))
      (node (ref "J4") (pin "G4") (pinfunction "GND_4_G4") (pintype "bidirectional"))
      (node (ref "J4") (pin "P6") (pinfunction "VSS_P6") (pintype "bidirectional"))
      (node (ref "MCP73831") (pin "2") (pinfunction "VSS_2") (pintype "power_in"))
      (node (ref "R1_PWRUSB") (pin "1") (pinfunction "1_1") (pintype "passive"))
      (node (ref "R2") (pin "1") (pinfunction "1_1") (pintype "passive"))
      (node (ref "R2-USB") (pin "2") (pinfunction "2_2") (pintype "passive"))
      (node (ref "R2-USB1") (pin "1") (pinfunction "1_1") (pintype "passive"))
      (node (ref "R2_BAT") (pin "1") (pinfunction "1_1") (pintype "passive"))
      (node (ref "R4") (pin "1") (pinfunction "1_1") (pintype "passive"))
      (node (ref "RESET_BUTTON") (pin "1") (pinfunction "1_1") (pintype "passive"))
      (node (ref "RESET_BUTTON") (pin "2") (pinfunction "2_2") (pintype "passive"))
      (node (ref "SENSOR2") (pin "1") (pinfunction "GND_1") (pintype "power_in"))
      (node (ref "SENSOR2") (pin "5") (pinfunction "SDO_5") (pintype "bidirectional"))
      (node (ref "SENSOR2") (pin "7") (pinfunction "GND_7") (pintype "power_in"))
      (node (ref "SJ1") (pin "1") (pinfunction "1_1") (pintype "passive"))
      (node (ref "TP4") (pin "TP") (pinfunction "TP_TP") (pintype "input"))
      (node (ref "TP_GND") (pin "TP") (pinfunction "TP_TP") (pintype "input"))
      (node (ref "U1") (pin "4") (pinfunction "GND_4") (pintype "power_in"))
      (node (ref "U1") (pin "9") (pinfunction "EXP_9") (pintype "passive"))
      (node (ref "U2") (pin "1") (pinfunction "GND_1") (pintype "power_in"))
      (node (ref "U2") (pin "28") (pinfunction "GND_28") (pintype "power_in"))
      (node (ref "U2") (pin "29_1") (pinfunction "GND_29_1") (pintype "power_in"))
      (node (ref "U2") (pin "29_2") (pinfunction "GND_29_2") (pintype "power_in"))
      (node (ref "U2") (pin "29_3") (pinfunction "GND_29_3") (pintype "power_in"))
      (node (ref "U2") (pin "29_4") (pinfunction "GND_29_4") (pintype "power_in"))
      (node (ref "U2") (pin "29_5") (pinfunction "GND_29_5") (pintype "power_in"))
      (node (ref "U2") (pin "29_6") (pinfunction "GND_29_6") (pintype "power_in"))
      (node (ref "U2") (pin "29_7") (pinfunction "GND_29_7") (pintype "power_in"))
      (node (ref "U2") (pin "29_8") (pinfunction "GND_29_8") (pintype "power_in"))
      (node (ref "U2") (pin "29_9") (pinfunction "GND_29_9") (pintype "power_in"))
      (node (ref "U3") (pin "13") (pinfunction "GND_13") (pintype "power_in"))
      (node (ref "U4") (pin "1") (pinfunction "CTG_1") (pintype "power_in"))
      (node (ref "U4") (pin "4") (pinfunction "GND_4") (pintype "power_in"))
      (node (ref "U4") (pin "6") (pinfunction "QSTRT_6") (pintype "input"))
      (node (ref "U4") (pin "9") (pinfunction "EP_9") (pintype "power_in"))
    )
    (net (code "15") (name "GPIO8") (class "Default")
      (node (ref "R1") (pin "2") (pinfunction "2_2") (pintype "passive"))
      (node (ref "U2") (pin "10") (pinfunction "IO8_10") (pintype "bidirectional"))
    )
    (net (code "16") (name "I2C_PW") (class "Default")
      (node (ref "C1") (pin "1") (pinfunction "1_1") (pintype "passive"))
      (node (ref "C2") (pin "1") (pinfunction "1_1") (pintype "passive"))
      (node (ref "R1_PINH") (pin "2") (pinfunction "2_2") (pintype "passive"))
      (node (ref "R2-PINH") (pin "2") (pinfunction "2_2") (pintype "passive"))
      (node (ref "SENSOR2") (pin "2") (pinfunction "CSB_2") (pintype "input"))
      (node (ref "SENSOR2") (pin "6") (pinfunction "VDDIO_6") (pintype "power_in"))
      (node (ref "SENSOR2") (pin "8") (pinfunction "VDD_8") (pintype "power_in"))
      (node (ref "U2") (pin "17") (pinfunction "IO19_17") (pintype "bidirectional"))
    )
    (net (code "17") (name "INT_RTC") (class "Default")
      (node (ref "R1_PINH1") (pin "1") (pinfunction "1_1") (pintype "passive"))
      (node (ref "TP_INT_RTC") (pin "TP") (pinfunction "TP_TP") (pintype "input"))
      (node (ref "U2") (pin "8") (pinfunction "IO0_8") (pintype "bidirectional"))
      (node (ref "U3") (pin "3") (pinfunction "SQW/~{INT}_3") (pintype "output"))
    )
    (net (code "18") (name "IO{slash}BOOT") (class "Default")
      (node (ref "BOOT_BUTTON") (pin "3") (pinfunction "3_3") (pintype "passive"))
      (node (ref "BOOT_BUTTON") (pin "4") (pinfunction "4_4") (pintype "passive"))
      (node (ref "C6") (pin "1") (pinfunction "1_1") (pintype "passive"))
      (node (ref "R_BOOT") (pin "1") (pinfunction "1_1") (pintype "passive"))
      (node (ref "U2") (pin "15") (pinfunction "IO9_15") (pintype "bidirectional"))
    )
    (net (code "19") (name "IO{slash}CHANGE") (class "Default")
      (node (ref "C10") (pin "1") (pinfunction "1_1") (pintype "passive"))
      (node (ref "CHANGE_BUTTON") (pin "3") (pinfunction "3_3") (pintype "passive"))
      (node (ref "CHANGE_BUTTON") (pin "4") (pinfunction "4_4") (pintype "passive"))
      (node (ref "R_CHANGE") (pin "1") (pinfunction "1_1") (pintype "passive"))
      (node (ref "U2") (pin "23") (pinfunction "IO15_23") (pintype "bidirectional"))
    )
    (net (code "20") (name "MISO") (class "Default")
      (node (ref "D12") (pin "2") (pinfunction "2_2") (pintype "passive"))
      (node (ref "J4") (pin "P7") (pinfunction "DAT0_P7") (pintype "bidirectional"))
      (node (ref "R8") (pin "1") (pinfunction "1_1") (pintype "passive"))
      (node (ref "TP_MISO") (pin "TP") (pinfunction "TP_TP") (pintype "input"))
      (node (ref "U1") (pin "2") (pinfunction "DO(IO1)_2") (pintype "bidirectional"))
      (node (ref "U2") (pin "27") (pinfunction "IO2_27") (pintype "bidirectional"))
    )
    (net (code "21") (name "MOSI") (class "Default")
      (node (ref "D11") (pin "2") (pinfunction "2_2") (pintype "passive"))
      (node (ref "J1") (pin "14") (pinfunction "14_14") (pintype "bidirectional"))
      (node (ref "J4") (pin "P3") (pinfunction "CMD_P3") (pintype "bidirectional"))
      (node (ref "R7") (pin "1") (pinfunction "1_1") (pintype "passive"))
      (node (ref "TP_MOSI") (pin "TP") (pinfunction "TP_TP") (pintype "input"))
      (node (ref "U1") (pin "5") (pinfunction "DI(IO0)_5") (pintype "bidirectional"))
      (node (ref "U2") (pin "7") (pinfunction "IO7_7") (pintype "bidirectional"))
    )
    (net (code "22") (name "Net-(CHG_LED-PadC)") (class "Default")
      (node (ref "CHG_LED") (pin "C") (pinfunction "C_C") (pintype "passive"))
      (node (ref "R1_BAT") (pin "1") (pinfunction "1_1") (pintype "passive"))
    )
    (net (code "23") (name "Net-(D2-CATHODE)") (class "Default")
      (node (ref "C1_BAT1") (pin "1") (pinfunction "1_1") (pintype "passive"))
      (node (ref "D2") (pin "1") (pinfunction "CATHODE_1") (pintype "bidirectional"))
      (node (ref "IC4") (pin "1") (pinfunction "VIN_1") (pintype "bidirectional"))
      (node (ref "IC4") (pin "3") (pinfunction "CE_3") (pintype "bidirectional"))
      (node (ref "Q1") (pin "2") (pinfunction "S_2") (pintype "bidirectional"))
    )
    (net (code "24") (name "Net-(D3-A)") (class "Default")
      (node (ref "C4") (pin "1") (pinfunction "1_1") (pintype "passive"))
      (node (ref "D3") (pin "2") (pinfunction "A_2") (pintype "bidirectional"))
      (node (ref "D4") (pin "1") (pinfunction "K_1") (pintype "bidirectional"))
    )
    (net (code "25") (name "Net-(D7-CATHODE)") (class "Default")
      (node (ref "D7") (pin "1") (pinfunction "CATHODE_1") (pintype "bidirectional"))
      (node (ref "R_CAPACITOR") (pin "1") (pinfunction "1_1") (pintype "passive"))
    )
    (net (code "26") (name "Net-(EPD_C1-Pad2)") (class "Default")
      (node (ref "EPD_C1") (pin "2") (pinfunction "2_2") (pintype "passive"))
      (node (ref "J1") (pin "4") (pinfunction "4_4") (pintype "bidirectional"))
    )
    (net (code "27") (name "Net-(EPD_C2-Pad2)") (class "Default")
      (node (ref "EPD_C2") (pin "2") (pinfunction "2_2") (pintype "passive"))
      (node (ref "J1") (pin "5") (pinfunction "5_5") (pintype "bidirectional"))
    )
    (net (code "28") (name "Net-(EPD_C6-Pad2)") (class "Default")
      (node (ref "EPD_C6") (pin "2") (pinfunction "2_2") (pintype "passive"))
      (node (ref "J1") (pin "18") (pinfunction "18_18") (pintype "bidirectional"))
    )
    (net (code "29") (name "Net-(EPD_C7-Pad2)") (class "Default")
      (node (ref "EPD_C7") (pin "2") (pinfunction "2_2") (pintype "passive"))
      (node (ref "J1") (pin "19") (pinfunction "19_19") (pintype "bidirectional"))
    )
    (net (code "30") (name "Net-(EPD_C8-Pad2)") (class "Default")
      (node (ref "EPD_C8") (pin "2") (pinfunction "2_2") (pintype "passive"))
      (node (ref "J1") (pin "20") (pinfunction "20_20") (pintype "bidirectional"))
    )
    (net (code "31") (name "Net-(EPD_C10-Pad2)") (class "Default")
      (node (ref "EPD_C10") (pin "2") (pinfunction "2_2") (pintype "passive"))
      (node (ref "J1") (pin "22") (pinfunction "22_22") (pintype "bidirectional"))
    )
    (net (code "32") (name "Net-(EPD_C12-Pad2)") (class "Default")
      (node (ref "EPD_C12") (pin "2") (pinfunction "2_2") (pintype "passive"))
      (node (ref "J1") (pin "24") (pinfunction "24_24") (pintype "bidirectional"))
    )
    (net (code "33") (name "Net-(IC1-CT)") (class "Default")
      (node (ref "C_DELAY") (pin "1") (pinfunction "1_1") (pintype "passive"))
      (node (ref "IC1") (pin "5") (pinfunction "CT_5") (pintype "bidirectional"))
    )
    (net (code "34") (name "Net-(J2-PadA5)") (class "Default")
      (node (ref "J2") (pin "A5") (pinfunction "A5_A5") (pintype "bidirectional"))
      (node (ref "R2-USB1") (pin "2") (pinfunction "2_2") (pintype "passive"))
    )
    (net (code "35") (name "Net-(J2-PadB5)") (class "Default")
      (node (ref "J2") (pin "B5") (pinfunction "B5_B5") (pintype "bidirectional"))
      (node (ref "R2-USB") (pin "1") (pinfunction "1_1") (pintype "passive"))
    )
    (net (code "36") (name "Net-(MCP73831-PROG)") (class "Default")
      (node (ref "MCP73831") (pin "5") (pinfunction "PROG_5") (pintype "input"))
      (node (ref "R2_BAT") (pin "2") (pinfunction "2_2") (pintype "passive"))
    )
    (net (code "37") (name "Net-(MCP73831-STAT)") (class "Default")
      (node (ref "MCP73831") (pin "1") (pinfunction "STAT_1") (pintype "output"))
      (node (ref "R1_BAT") (pin "2") (pinfunction "2_2") (pintype "passive"))
    )
    (net (code "38") (name "PREVGH") (class "Default")
      (node (ref "D5") (pin "1") (pinfunction "K_1") (pintype "bidirectional"))
      (node (ref "EPD_C9") (pin "2") (pinfunction "2_2") (pintype "passive"))
      (node (ref "J1") (pin "21") (pinfunction "21_21") (pintype "bidirectional"))
    )
    (net (code "39") (name "PREVGL") (class "Default")
      (node (ref "D4") (pin "2") (pinfunction "A_2") (pintype "bidirectional"))
      (node (ref "EPD_C11") (pin "2") (pinfunction "2_2") (pintype "passive"))
      (node (ref "J1") (pin "23") (pinfunction "23_23") (pintype "bidirectional"))
    )
    (net (code "40") (name "RESE") (class "Default")
      (node (ref "J1") (pin "3") (pinfunction "3_3") (pintype "bidirectional"))
      (node (ref "Q3") (pin "2") (pinfunction "S_2") (pintype "bidirectional"))
      (node (ref "R3") (pin "2") (pinfunction "2_2") (pintype "passive"))
    )
    (net (code "41") (name "RESET") (class "Default")
      (node (ref "C5") (pin "1") (pinfunction "1_1") (pintype "passive"))
      (node (ref "IC1") (pin "1") (pinfunction "VOUT_1") (pintype "bidirectional"))
      (node (ref "RESET_BUTTON") (pin "3") (pinfunction "3_3") (pintype "passive"))
      (node (ref "RESET_BUTTON") (pin "4") (pinfunction "4_4") (pintype "passive"))
      (node (ref "R_RESET") (pin "1") (pinfunction "1_1") (pintype "passive"))
      (node (ref "U2") (pin "3") (pinfunction "EN_3") (pintype "input"))
    )
    (net (code "42") (name "RESE`") (class "Default")
      (node (ref "R2") (pin "2") (pinfunction "2_2") (pintype "passive"))
      (node (ref "R3") (pin "1") (pinfunction "1_1") (pintype "passive"))
      (node (ref "SJ1") (pin "2") (pinfunction "2_2") (pintype "passive"))
    )
    (net (code "43") (name "RTC_RST") (class "Default")
      (node (ref "U2") (pin "16") (pinfunction "IO18_16") (pintype "bidirectional"))
      (node (ref "U3") (pin "4") (pinfunction "~{RST}_4") (pintype "input"))
    )
    (net (code "44") (name "RX") (class "Default")
      (node (ref "TP_RX") (pin "TP") (pinfunction "TP_TP") (pintype "input"))
      (node (ref "U2") (pin "24") (pinfunction "RXD0/GPIO17_24") (pintype "bidirectional"))
    )
    (net (code "45") (name "SCK") (class "Default")
      (node (ref "D10") (pin "2") (pinfunction "2_2") (pintype "passive"))
      (node (ref "J1") (pin "13") (pinfunction "13_13") (pintype "bidirectional"))
      (node (ref "J4") (pin "P5") (pinfunction "CLK_P5") (pintype "bidirectional"))
      (node (ref "R6") (pin "1") (pinfunction "1_1") (pintype "passive"))
      (node (ref "TP_SCK") (pin "TP") (pinfunction "TP_TP") (pintype "input"))
      (node (ref "U1") (pin "6") (pinfunction "CLK_6") (pintype "input"))
      (node (ref "U2") (pin "6") (pinfunction "IO6_6") (pintype "bidirectional"))
    )
    (net (code "46") (name "SCL") (class "Default")
      (node (ref "J3") (pin "4") (pinfunction "4_4") (pintype "passive"))
      (node (ref "R2-PINH") (pin "1") (pinfunction "1_1") (pintype "passive"))
      (node (ref "SENSOR2") (pin "4") (pinfunction "SCK_4") (pintype "input"))
      (node (ref "U2") (pin "20") (pinfunction "IO22_20") (pintype "bidirectional"))
      (node (ref "U3") (pin "16") (pinfunction "SCL_16") (pintype "input"))
      (node (ref "U4") (pin "7") (pinfunction "SCL_7") (pintype "input"))
    )
    (net (code "47") (name "SDA") (class "Default")
      (node (ref "J3") (pin "3") (pinfunction "3_3") (pintype "passive"))
      (node (ref "R1_PINH") (pin "1") (pinfunction "1_1") (pintype "passive"))
      (node (ref "SENSOR2") (pin "3") (pinfunction "SDI_3") (pintype "bidirectional"))
      (node (ref "U2") (pin "19") (pinfunction "IO21_19") (pintype "bidirectional"))
      (node (ref "U3") (pin "15") (pinfunction "SDA_15") (pintype "bidirectional"))
      (node (ref "U4") (pin "8") (pinfunction "SDA_8") (pintype "bidirectional"))
    )
    (net (code "48") (name "SRC") (class "Default")
      (node (ref "C4") (pin "2") (pinfunction "2_2") (pintype "passive"))
      (node (ref "D5") (pin "2") (pinfunction "A_2") (pintype "bidirectional"))
      (node (ref "L1") (pin "1") (pinfunction "1_1") (pintype "passive"))
      (node (ref "Q3") (pin "3") (pinfunction "D_3") (pintype "bidirectional"))
    )
    (net (code "49") (name "SS_SD") (class "Default")
      (node (ref "D8") (pin "2") (pinfunction "2_2") (pintype "passive"))
      (node (ref "J4") (pin "P2") (pinfunction "CD/DAT3_P2") (pintype "bidirectional"))
      (node (ref "R10") (pin "1") (pinfunction "1_1") (pintype "passive"))
      (node (ref "U2") (pin "4") (pinfunction "IO4_4") (pintype "bidirectional"))
    )
    (net (code "50") (name "TX") (class "Default")
      (node (ref "TP_TX") (pin "TP") (pinfunction "TP_TP") (pintype "input"))
      (node (ref "U2") (pin "25") (pinfunction "TXD0/GPIO16_25") (pintype "bidirectional"))
    )
    (net (code "51") (name "USB_D+") (class "Default")
      (node (ref "D1") (pin "1") (pinfunction "I/O1_1_1") (pintype "bidirectional"))
      (node (ref "U2") (pin "14") (pinfunction "IO13_14") (pintype "bidirectional"))
    )
    (net (code "52") (name "USB_D-") (class "Default")
      (node (ref "D1") (pin "3") (pinfunction "I/O2_1_3") (pintype "bidirectional"))
      (node (ref "U2") (pin "13") (pinfunction "IO12_13") (pintype "bidirectional"))
    )
    (net (code "53") (name "VBAT") (class "Default")
      (node (ref "C2_BAT") (pin "1") (pinfunction "1_1") (pintype "passive"))
      (node (ref "MCP73831") (pin "3") (pinfunction "VBAT_3") (pintype "power_in"))
      (node (ref "Q1") (pin "3") (pinfunction "D_3") (pintype "bidirectional"))
      (node (ref "TP_VBAT") (pin "TP") (pinfunction "TP_TP") (pintype "input"))
      (node (ref "U4") (pin "2") (pinfunction "CELL_2") (pintype "power_in"))
      (node (ref "U4") (pin "3") (pinfunction "VDD_3") (pintype "power_in"))
    )
    (net (code "54") (name "VBUS") (class "Default")
      (node (ref "C1_BAT") (pin "1") (pinfunction "1_1") (pintype "passive"))
      (node (ref "C4_USB") (pin "1") (pinfunction "1_1") (pintype "passive"))
      (node (ref "C5_USB") (pin "1") (pinfunction "1_1") (pintype "passive"))
      (node (ref "CHG_LED") (pin "A") (pinfunction "A_A") (pintype "passive"))
      (node (ref "D1") (pin "5") (pinfunction "VBUS_5") (pintype "bidirectional"))
      (node (ref "D2") (pin "2") (pinfunction "ANODE_2") (pintype "bidirectional"))
      (node (ref "MCP73831") (pin "4") (pinfunction "VIN_4") (pintype "power_in"))
      (node (ref "PFMF.050.1") (pin "2") (pinfunction "2_2") (pintype "passive"))
      (node (ref "Q1") (pin "1") (pinfunction "G_1") (pintype "bidirectional"))
      (node (ref "R1_PWRUSB") (pin "2") (pinfunction "2_2") (pintype "passive"))
      (node (ref "TP_VBUS") (pin "TP") (pinfunction "TP_TP") (pintype "input"))
    )
    (net (code "55") (name "VRTC") (class "Default")
      (node (ref "C11") (pin "1") (pinfunction "1_1") (pintype "passive"))
      (node (ref "C8") (pin "1") (pinfunction "1_1") (pintype "passive"))
      (node (ref "R_CAPACITOR") (pin "2") (pinfunction "2_2") (pintype "passive"))
      (node (ref "U3") (pin "14") (pinfunction "VBAT_14") (pintype "power_in"))
    )
    (net (code "56") (name "VUSB") (class "Default")
      (node (ref "J2") (pin "A4") (pinfunction "A4_A4") (pintype "bidirectional"))
      (node (ref "J2") (pin "A9") (pinfunction "A9_A9") (pintype "bidirectional"))
      (node (ref "J2") (pin "B4") (pinfunction "B4_B4") (pintype "bidirectional"))
      (node (ref "J2") (pin "B9") (pinfunction "B9_B9") (pintype "bidirectional"))
      (node (ref "PFMF.050.1") (pin "1") (pinfunction "1_1") (pintype "passive"))
    )
    (net (code "57") (name "unconnected-(IC1-NC-Pad4)") (class "Default")
      (node (ref "IC1") (pin "4") (pinfunction "NC_4") (pintype "no_connect"))
    )
    (net (code "58") (name "unconnected-(IC4-NC-Pad4)") (class "Default")
      (node (ref "IC4") (pin "4") (pinfunction "NC_4") (pintype "no_connect"))
    )
    (net (code "59") (name "unconnected-(J1-Pad1)") (class "Default")
      (node (ref "J1") (pin "1") (pinfunction "1_1") (pintype "bidirectional"))
    )
    (net (code "60") (name "unconnected-(J1-Pad6)") (class "Default")
      (node (ref "J1") (pin "6") (pinfunction "6_6") (pintype "bidirectional"))
    )
    (net (code "61") (name "unconnected-(J1-Pad7)") (class "Default")
      (node (ref "J1") (pin "7") (pinfunction "7_7") (pintype "bidirectional"))
    )
    (net (code "62") (name "unconnected-(J2-PadA8)") (class "Default")
      (node (ref "J2") (pin "A8") (pinfunction "A8_A8") (pintype "bidirectional"))
    )
    (net (code "63") (name "unconnected-(J2-PadB8)") (class "Default")
      (node (ref "J2") (pin "B8") (pinfunction "B8_B8") (pintype "bidirectional"))
    )
    (net (code "64") (name "unconnected-(J4-DAT1-PadP8)") (class "Default")
      (node (ref "J4") (pin "P8") (pinfunction "DAT1_P8") (pintype "bidirectional"))
    )
    (net (code "65") (name "unconnected-(J4-DAT2-PadP1)") (class "Default")
      (node (ref "J4") (pin "P1") (pinfunction "DAT2_P1") (pintype "bidirectional"))
    )
    (net (code "66") (name "unconnected-(J4-DETECTION_1-PadS1)") (class "Default")
      (node (ref "J4") (pin "S1") (pinfunction "DETECTION_1_S1") (pintype "bidirectional"))
    )
    (net (code "67") (name "unconnected-(J4-DETECTION_2-PadS2)") (class "Default")
      (node (ref "J4") (pin "S2") (pinfunction "DETECTION_2_S2") (pintype "bidirectional"))
    )
    (net (code "68") (name "unconnected-(U2-NC-Pad22)") (class "Default")
      (node (ref "U2") (pin "22") (pinfunction "NC_22") (pintype "no_connect"))
    )
    (net (code "69") (name "unconnected-(U4-~{ALERT}-Pad5)") (class "Default")
      (node (ref "U4") (pin "5") (pinfunction "~{ALERT}_5") (pintype "output"))
    )
  )
)
